# motherboardV2.net
KiCad netlist of a schematic drawn in EAGLE
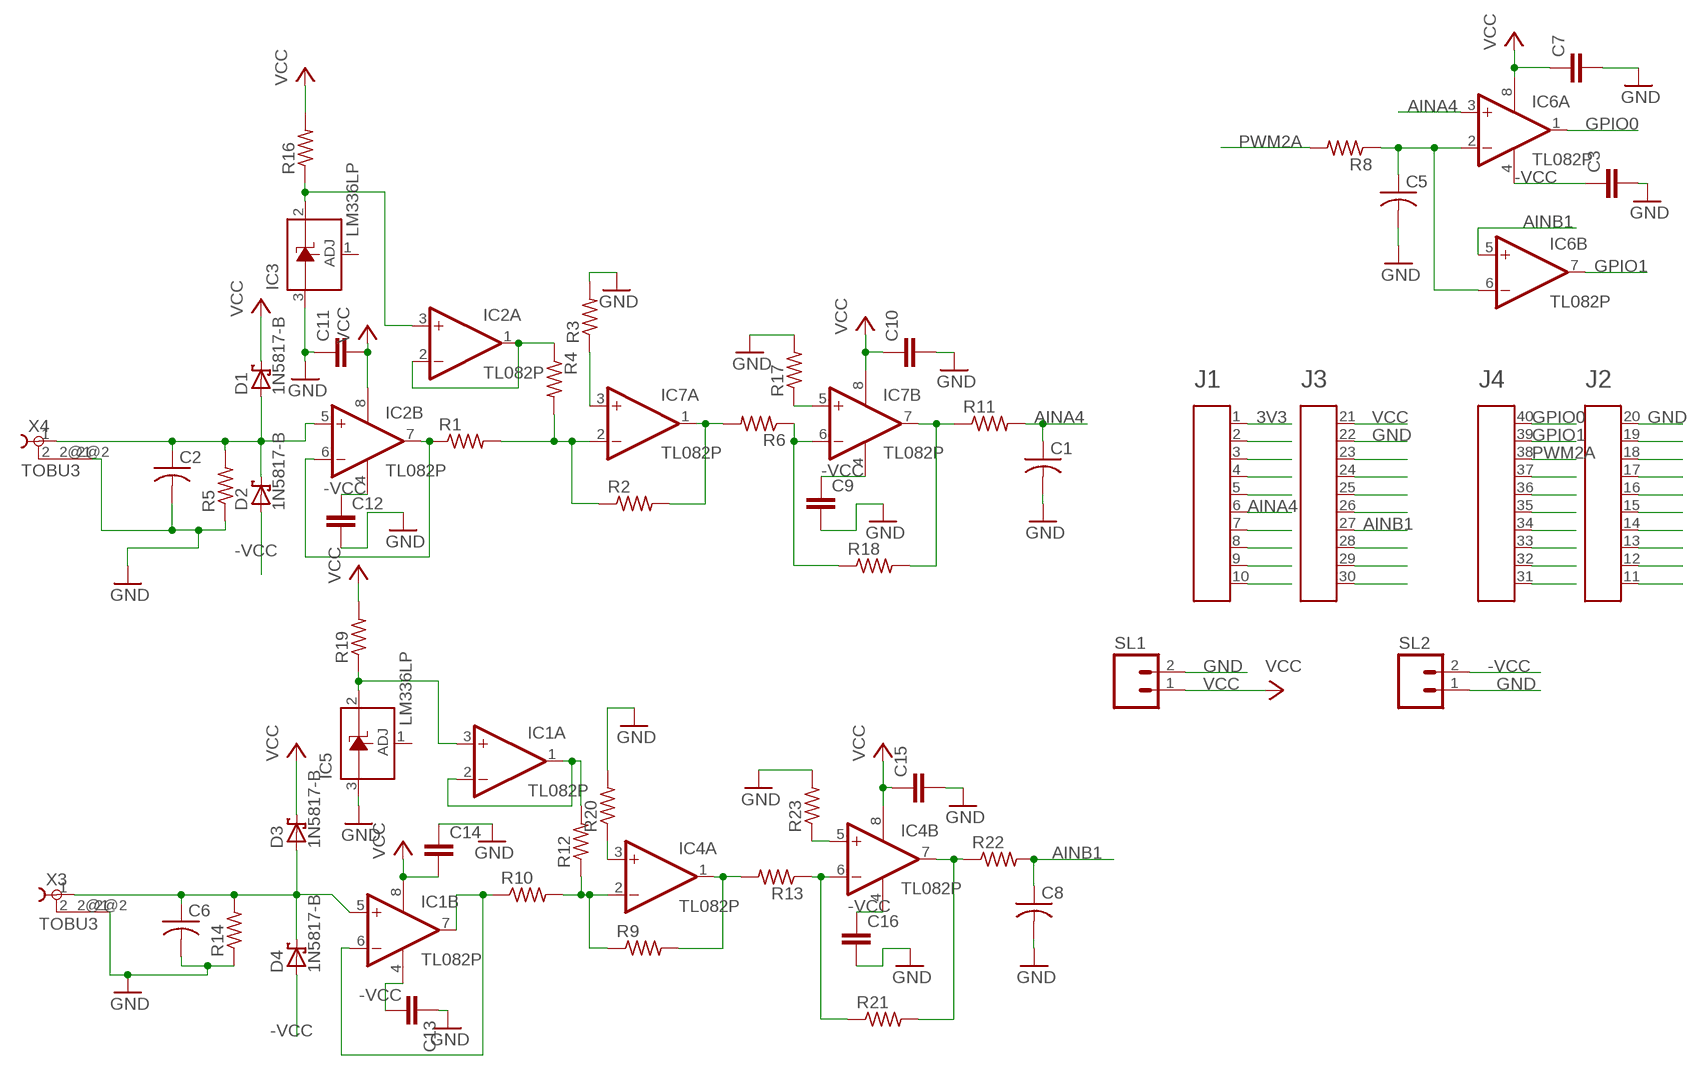
[diagram p0: schematic, sheet 1]

(export (version "E")
  (design (tool "Eeschema 10.0.6"))
  (components
    (comp (ref "A1")
      (value "HEADER4X10-BOOSTERPACK")
      (footprint "eagle-import:4X10-BOOSTERPACK")
      (libsource (lib "eagle-import") (part "HEADER4X10-BOOSTERPACK"))
    )
    (comp (ref "C1")
      (value "C-US025-025X050")
      (footprint "eagle-import:C025-025X050")
      (libsource (lib "eagle-import") (part "C-US025-025X050"))
    )
    (comp (ref "C2")
      (value "C-US025-025X050")
      (footprint "eagle-import:C025-025X050")
      (libsource (lib "eagle-import") (part "C-US025-025X050"))
    )
    (comp (ref "C3")
      (value "C-EU025-025X050")
      (footprint "eagle-import:C025-025X050")
      (libsource (lib "eagle-import") (part "C-EU025-025X050"))
    )
    (comp (ref "C5")
      (value "C-US025-025X050")
      (footprint "eagle-import:C025-025X050")
      (libsource (lib "eagle-import") (part "C-US025-025X050"))
    )
    (comp (ref "C6")
      (value "C-US025-025X050")
      (footprint "eagle-import:C025-025X050")
      (libsource (lib "eagle-import") (part "C-US025-025X050"))
    )
    (comp (ref "C7")
      (value "C-EU025-025X050")
      (footprint "eagle-import:C025-025X050")
      (libsource (lib "eagle-import") (part "C-EU025-025X050"))
    )
    (comp (ref "C8")
      (value "C-US025-025X050")
      (footprint "eagle-import:C025-025X050")
      (libsource (lib "eagle-import") (part "C-US025-025X050"))
    )
    (comp (ref "C9")
      (value "C-EU025-025X050")
      (footprint "eagle-import:C025-025X050")
      (libsource (lib "eagle-import") (part "C-EU025-025X050"))
    )
    (comp (ref "C10")
      (value "C-EU025-025X050")
      (footprint "eagle-import:C025-025X050")
      (libsource (lib "eagle-import") (part "C-EU025-025X050"))
    )
    (comp (ref "C11")
      (value "C-EU025-025X050")
      (footprint "eagle-import:C025-025X050")
      (libsource (lib "eagle-import") (part "C-EU025-025X050"))
    )
    (comp (ref "C12")
      (value "C-EU025-030X050")
      (footprint "eagle-import:C025-030X050")
      (libsource (lib "eagle-import") (part "C-EU025-030X050"))
    )
    (comp (ref "C13")
      (value "C-EU025-025X050")
      (footprint "eagle-import:C025-025X050")
      (libsource (lib "eagle-import") (part "C-EU025-025X050"))
    )
    (comp (ref "C14")
      (value "C-EU025-025X050")
      (footprint "eagle-import:C025-025X050")
      (libsource (lib "eagle-import") (part "C-EU025-025X050"))
    )
    (comp (ref "C15")
      (value "C-EU025-025X050")
      (footprint "eagle-import:C025-025X050")
      (libsource (lib "eagle-import") (part "C-EU025-025X050"))
    )
    (comp (ref "C16")
      (value "C-EU025-025X050")
      (footprint "eagle-import:C025-025X050")
      (libsource (lib "eagle-import") (part "C-EU025-025X050"))
    )
    (comp (ref "D1")
      (value "1N5817-B")
      (footprint "eagle-import:DO41-7.6")
      (libsource (lib "eagle-import") (part "1N5817-B"))
    )
    (comp (ref "D2")
      (value "1N5817-B")
      (footprint "eagle-import:DO41-7.6")
      (libsource (lib "eagle-import") (part "1N5817-B"))
    )
    (comp (ref "D3")
      (value "1N5817-B")
      (footprint "eagle-import:DO41-7.6")
      (libsource (lib "eagle-import") (part "1N5817-B"))
    )
    (comp (ref "D4")
      (value "1N5817-B")
      (footprint "eagle-import:DO41-7.6")
      (libsource (lib "eagle-import") (part "1N5817-B"))
    )
    (comp (ref "IC1")
      (value "TL082P")
      (footprint "eagle-import:DIL08")
      (libsource (lib "eagle-import") (part "TL082P"))
    )
    (comp (ref "IC2")
      (value "TL082P")
      (footprint "eagle-import:DIL08")
      (libsource (lib "eagle-import") (part "TL082P"))
    )
    (comp (ref "IC3")
      (value "LM336LP")
      (footprint "eagle-import:TO92")
      (libsource (lib "eagle-import") (part "LM336LP"))
    )
    (comp (ref "IC4")
      (value "TL082P")
      (footprint "eagle-import:DIL08")
      (libsource (lib "eagle-import") (part "TL082P"))
    )
    (comp (ref "IC5")
      (value "LM336LP")
      (footprint "eagle-import:TO92")
      (libsource (lib "eagle-import") (part "LM336LP"))
    )
    (comp (ref "IC6")
      (value "TL082P")
      (footprint "eagle-import:DIL08")
      (libsource (lib "eagle-import") (part "TL082P"))
    )
    (comp (ref "IC7")
      (value "TL082P")
      (footprint "eagle-import:DIL08")
      (libsource (lib "eagle-import") (part "TL082P"))
    )
    (comp (ref "R1")
      (value "R-US_0207/7")
      (footprint "eagle-import:0207_7")
      (libsource (lib "eagle-import") (part "resistor_R-US_0207/7"))
    )
    (comp (ref "R2")
      (value "R-US_0207/7")
      (footprint "eagle-import:0207_7")
      (libsource (lib "eagle-import") (part "resistor_R-US_0207/7"))
    )
    (comp (ref "R3")
      (value "R-US_0207/7")
      (footprint "eagle-import:0207_7")
      (libsource (lib "eagle-import") (part "resistor_R-US_0207/7"))
    )
    (comp (ref "R4")
      (value "R-US_0207/7")
      (footprint "eagle-import:0207_7")
      (libsource (lib "eagle-import") (part "resistor_R-US_0207/7"))
    )
    (comp (ref "R5")
      (value "R-US_0207/7")
      (footprint "eagle-import:0207_7")
      (libsource (lib "eagle-import") (part "resistor_R-US_0207/7"))
    )
    (comp (ref "R6")
      (value "R-US_0207/7")
      (footprint "eagle-import:0207_7")
      (libsource (lib "eagle-import") (part "resistor_R-US_0207/7"))
    )
    (comp (ref "R8")
      (value "R-US_0207/7")
      (footprint "eagle-import:0207_7")
      (libsource (lib "eagle-import") (part "R-US_0207/7"))
    )
    (comp (ref "R9")
      (value "R-US_0207/7")
      (footprint "eagle-import:0207_7")
      (libsource (lib "eagle-import") (part "resistor_R-US_0207/7"))
    )
    (comp (ref "R10")
      (value "R-US_0207/7")
      (footprint "eagle-import:0207_7")
      (libsource (lib "eagle-import") (part "resistor_R-US_0207/7"))
    )
    (comp (ref "R11")
      (value "R-US_0207/7")
      (footprint "eagle-import:0207_7")
      (libsource (lib "eagle-import") (part "resistor_R-US_0207/7"))
    )
    (comp (ref "R12")
      (value "R-US_0207/7")
      (footprint "eagle-import:0207_7")
      (libsource (lib "eagle-import") (part "resistor_R-US_0207/7"))
    )
    (comp (ref "R13")
      (value "R-US_0207/7")
      (footprint "eagle-import:0207_7")
      (libsource (lib "eagle-import") (part "resistor_R-US_0207/7"))
    )
    (comp (ref "R14")
      (value "R-US_0207/7")
      (footprint "eagle-import:0207_7")
      (libsource (lib "eagle-import") (part "resistor_R-US_0207/7"))
    )
    (comp (ref "R16")
      (value "R-US_0207/7")
      (footprint "eagle-import:0207_7")
      (libsource (lib "eagle-import") (part "R-US_0207/7"))
    )
    (comp (ref "R17")
      (value "R-US_0207/7")
      (footprint "eagle-import:0207_7")
      (libsource (lib "eagle-import") (part "resistor_R-US_0207/7"))
    )
    (comp (ref "R18")
      (value "R-US_0207/7")
      (footprint "eagle-import:0207_7")
      (libsource (lib "eagle-import") (part "resistor_R-US_0207/7"))
    )
    (comp (ref "R19")
      (value "R-US_0207/7")
      (footprint "eagle-import:0207_7")
      (libsource (lib "eagle-import") (part "R-US_0207/7"))
    )
    (comp (ref "R20")
      (value "R-US_0207/7")
      (footprint "eagle-import:0207_7")
      (libsource (lib "eagle-import") (part "R-US_0207/7"))
    )
    (comp (ref "R21")
      (value "R-US_0207/7")
      (footprint "eagle-import:0207_7")
      (libsource (lib "eagle-import") (part "R-US_0207/7"))
    )
    (comp (ref "R22")
      (value "R-US_0207/7")
      (footprint "eagle-import:0207_7")
      (libsource (lib "eagle-import") (part "R-US_0207/7"))
    )
    (comp (ref "R23")
      (value "R-US_0207/7")
      (footprint "eagle-import:0207_7")
      (libsource (lib "eagle-import") (part "R-US_0207/7"))
    )
    (comp (ref "SL1")
      (value "M02")
      (footprint "eagle-import:02P")
      (libsource (lib "eagle-import") (part "M02"))
    )
    (comp (ref "SL2")
      (value "M02")
      (footprint "eagle-import:02P")
      (libsource (lib "eagle-import") (part "M02"))
    )
    (comp (ref "X3")
      (value "TOBU3")
      (footprint "eagle-import:TOBU3")
      (libsource (lib "eagle-import") (part "TOBU3"))
    )
    (comp (ref "X4")
      (value "TOBU3")
      (footprint "eagle-import:TOBU3")
      (libsource (lib "eagle-import") (part "TOBU3"))
    )
  )
  (nets
    (net (code "1") (name "/-VCC") (class "Default")
      (node (ref "C12") (pin "1") (pinfunction "1_1") (pintype "passive"))
      (node (ref "C13") (pin "2") (pinfunction "2_2") (pintype "passive"))
      (node (ref "C16") (pin "1") (pinfunction "1_1") (pintype "passive"))
      (node (ref "C3") (pin "1") (pinfunction "1_1") (pintype "passive"))
      (node (ref "C9") (pin "1") (pinfunction "1_1") (pintype "passive"))
      (node (ref "D2") (pin "A") (pinfunction "A_A") (pintype "passive"))
      (node (ref "D4") (pin "A") (pinfunction "A_A") (pintype "passive"))
      (node (ref "IC1") (pin "4") (pinfunction "V-_4") (pintype "power_in"))
      (node (ref "IC2") (pin "4") (pinfunction "V-_4") (pintype "power_in"))
      (node (ref "IC4") (pin "4") (pinfunction "V-_4") (pintype "power_in"))
      (node (ref "IC6") (pin "4") (pinfunction "V-_4") (pintype "power_in"))
      (node (ref "IC7") (pin "4") (pinfunction "V-_4") (pintype "power_in"))
      (node (ref "SL2") (pin "2") (pinfunction "2_2") (pintype "passive"))
    )
    (net (code "2") (name "/3V3") (class "Default")
      (node (ref "A1") (pin "1") (pinfunction "P$1_1") (pintype "bidirectional"))
    )
    (net (code "3") (name "/AINA4") (class "Default")
      (node (ref "A1") (pin "6") (pinfunction "P$6_6") (pintype "bidirectional"))
      (node (ref "C1") (pin "1") (pinfunction "1_1") (pintype "passive"))
      (node (ref "IC6") (pin "3") (pinfunction "+IN_3") (pintype "input"))
      (node (ref "R11") (pin "2") (pinfunction "2_2") (pintype "passive"))
    )
    (net (code "4") (name "/AINB1") (class "Default")
      (node (ref "A1") (pin "27") (pinfunction "P$27_27") (pintype "bidirectional"))
      (node (ref "C8") (pin "1") (pinfunction "1_1") (pintype "passive"))
      (node (ref "IC6") (pin "5") (pinfunction "+IN_5") (pintype "input"))
      (node (ref "R22") (pin "2") (pinfunction "2_2") (pintype "passive"))
    )
    (net (code "5") (name "/GPIO0") (class "Default")
      (node (ref "A1") (pin "40") (pinfunction "P$40_40") (pintype "bidirectional"))
      (node (ref "IC6") (pin "1") (pinfunction "OUT_1") (pintype "output"))
    )
    (net (code "6") (name "/GPIO1") (class "Default")
      (node (ref "A1") (pin "39") (pinfunction "P$39_39") (pintype "bidirectional"))
      (node (ref "IC6") (pin "7") (pinfunction "OUT_7") (pintype "output"))
    )
    (net (code "7") (name "/PWM2A") (class "Default")
      (node (ref "A1") (pin "38") (pinfunction "P$38_38") (pintype "bidirectional"))
      (node (ref "R8") (pin "2") (pinfunction "2_2") (pintype "passive"))
    )
    (net (code "8") (name "GND") (class "Default")
      (node (ref "A1") (pin "20") (pinfunction "P$20_20") (pintype "bidirectional"))
      (node (ref "A1") (pin "22") (pinfunction "P$22_22") (pintype "bidirectional"))
      (node (ref "C1") (pin "2") (pinfunction "2_2") (pintype "passive"))
      (node (ref "C10") (pin "2") (pinfunction "2_2") (pintype "passive"))
      (node (ref "C11") (pin "1") (pinfunction "1_1") (pintype "passive"))
      (node (ref "C12") (pin "2") (pinfunction "2_2") (pintype "passive"))
      (node (ref "C13") (pin "1") (pinfunction "1_1") (pintype "passive"))
      (node (ref "C14") (pin "1") (pinfunction "1_1") (pintype "passive"))
      (node (ref "C15") (pin "2") (pinfunction "2_2") (pintype "passive"))
      (node (ref "C16") (pin "2") (pinfunction "2_2") (pintype "passive"))
      (node (ref "C2") (pin "2") (pinfunction "2_2") (pintype "passive"))
      (node (ref "C3") (pin "2") (pinfunction "2_2") (pintype "passive"))
      (node (ref "C5") (pin "2") (pinfunction "2_2") (pintype "passive"))
      (node (ref "C6") (pin "2") (pinfunction "2_2") (pintype "passive"))
      (node (ref "C7") (pin "2") (pinfunction "2_2") (pintype "passive"))
      (node (ref "C8") (pin "2") (pinfunction "2_2") (pintype "passive"))
      (node (ref "C9") (pin "2") (pinfunction "2_2") (pintype "passive"))
      (node (ref "IC3") (pin "3") (pinfunction "A_3") (pintype "input"))
      (node (ref "IC5") (pin "3") (pinfunction "A_3") (pintype "input"))
      (node (ref "R14") (pin "1") (pinfunction "1_1") (pintype "passive"))
      (node (ref "R17") (pin "2") (pinfunction "2_2") (pintype "passive"))
      (node (ref "R20") (pin "2") (pinfunction "2_2") (pintype "passive"))
      (node (ref "R23") (pin "2") (pinfunction "2_2") (pintype "passive"))
      (node (ref "R3") (pin "2") (pinfunction "2_2") (pintype "passive"))
      (node (ref "R5") (pin "1") (pinfunction "1_1") (pintype "passive"))
      (node (ref "SL1") (pin "2") (pinfunction "2_2") (pintype "passive"))
      (node (ref "SL2") (pin "1") (pinfunction "1_1") (pintype "passive"))
      (node (ref "X3") (pin "2@2") (pinfunction "4_2@2") (pintype "passive"))
      (node (ref "X4") (pin "2@2") (pinfunction "4_2@2") (pintype "passive"))
    )
    (net (code "9") (name "Net-(IC1A-+IN)") (class "Default")
      (node (ref "IC1") (pin "3") (pinfunction "+IN_3") (pintype "input"))
      (node (ref "IC5") (pin "2") (pinfunction "C_2") (pintype "passive"))
      (node (ref "R19") (pin "1") (pinfunction "1_1") (pintype "passive"))
    )
    (net (code "10") (name "Net-(IC1A--IN)") (class "Default")
      (node (ref "IC1") (pin "1") (pinfunction "OUT_1") (pintype "output"))
      (node (ref "IC1") (pin "2") (pinfunction "-IN_2") (pintype "input"))
      (node (ref "R12") (pin "2") (pinfunction "2_2") (pintype "passive"))
    )
    (net (code "11") (name "Net-(IC1B-+IN)") (class "Default")
      (node (ref "C6") (pin "1") (pinfunction "1_1") (pintype "passive"))
      (node (ref "D3") (pin "A") (pinfunction "A_A") (pintype "passive"))
      (node (ref "D4") (pin "C") (pinfunction "C_C") (pintype "passive"))
      (node (ref "IC1") (pin "5") (pinfunction "+IN_5") (pintype "input"))
      (node (ref "R14") (pin "2") (pinfunction "2_2") (pintype "passive"))
      (node (ref "X3") (pin "1") (pinfunction "1_1") (pintype "passive"))
    )
    (net (code "12") (name "Net-(IC1B--IN)") (class "Default")
      (node (ref "IC1") (pin "6") (pinfunction "-IN_6") (pintype "input"))
      (node (ref "IC1") (pin "7") (pinfunction "OUT_7") (pintype "output"))
      (node (ref "R10") (pin "1") (pinfunction "1_1") (pintype "passive"))
    )
    (net (code "13") (name "Net-(IC2A-+IN)") (class "Default")
      (node (ref "IC2") (pin "3") (pinfunction "+IN_3") (pintype "input"))
      (node (ref "IC3") (pin "2") (pinfunction "C_2") (pintype "passive"))
      (node (ref "R16") (pin "1") (pinfunction "1_1") (pintype "passive"))
    )
    (net (code "14") (name "Net-(IC2A--IN)") (class "Default")
      (node (ref "IC2") (pin "1") (pinfunction "OUT_1") (pintype "output"))
      (node (ref "IC2") (pin "2") (pinfunction "-IN_2") (pintype "input"))
      (node (ref "R4") (pin "1") (pinfunction "1_1") (pintype "passive"))
    )
    (net (code "15") (name "Net-(IC2B-+IN)") (class "Default")
      (node (ref "C2") (pin "1") (pinfunction "1_1") (pintype "passive"))
      (node (ref "D1") (pin "A") (pinfunction "A_A") (pintype "passive"))
      (node (ref "D2") (pin "C") (pinfunction "C_C") (pintype "passive"))
      (node (ref "IC2") (pin "5") (pinfunction "+IN_5") (pintype "input"))
      (node (ref "R5") (pin "2") (pinfunction "2_2") (pintype "passive"))
      (node (ref "X4") (pin "1") (pinfunction "1_1") (pintype "passive"))
    )
    (net (code "16") (name "Net-(IC2B--IN)") (class "Default")
      (node (ref "IC2") (pin "6") (pinfunction "-IN_6") (pintype "input"))
      (node (ref "IC2") (pin "7") (pinfunction "OUT_7") (pintype "output"))
      (node (ref "R1") (pin "1") (pinfunction "1_1") (pintype "passive"))
    )
    (net (code "17") (name "Net-(IC4A-+IN)") (class "Default")
      (node (ref "IC4") (pin "3") (pinfunction "+IN_3") (pintype "input"))
      (node (ref "R20") (pin "1") (pinfunction "1_1") (pintype "passive"))
    )
    (net (code "18") (name "Net-(IC4A--IN)") (class "Default")
      (node (ref "IC4") (pin "2") (pinfunction "-IN_2") (pintype "input"))
      (node (ref "R10") (pin "2") (pinfunction "2_2") (pintype "passive"))
      (node (ref "R12") (pin "1") (pinfunction "1_1") (pintype "passive"))
      (node (ref "R9") (pin "1") (pinfunction "1_1") (pintype "passive"))
    )
    (net (code "19") (name "Net-(IC4A-OUT)") (class "Default")
      (node (ref "IC4") (pin "1") (pinfunction "OUT_1") (pintype "output"))
      (node (ref "R13") (pin "2") (pinfunction "2_2") (pintype "passive"))
      (node (ref "R9") (pin "2") (pinfunction "2_2") (pintype "passive"))
    )
    (net (code "20") (name "Net-(IC4B-+IN)") (class "Default")
      (node (ref "IC4") (pin "5") (pinfunction "+IN_5") (pintype "input"))
      (node (ref "R23") (pin "1") (pinfunction "1_1") (pintype "passive"))
    )
    (net (code "21") (name "Net-(IC4B--IN)") (class "Default")
      (node (ref "IC4") (pin "6") (pinfunction "-IN_6") (pintype "input"))
      (node (ref "R13") (pin "1") (pinfunction "1_1") (pintype "passive"))
      (node (ref "R21") (pin "1") (pinfunction "1_1") (pintype "passive"))
    )
    (net (code "22") (name "Net-(IC4B-OUT)") (class "Default")
      (node (ref "IC4") (pin "7") (pinfunction "OUT_7") (pintype "output"))
      (node (ref "R21") (pin "2") (pinfunction "2_2") (pintype "passive"))
      (node (ref "R22") (pin "1") (pinfunction "1_1") (pintype "passive"))
    )
    (net (code "23") (name "Net-(IC6A--IN)") (class "Default")
      (node (ref "C5") (pin "1") (pinfunction "1_1") (pintype "passive"))
      (node (ref "IC6") (pin "2") (pinfunction "-IN_2") (pintype "input"))
      (node (ref "IC6") (pin "6") (pinfunction "-IN_6") (pintype "input"))
      (node (ref "R8") (pin "1") (pinfunction "1_1") (pintype "passive"))
    )
    (net (code "24") (name "Net-(IC7A-+IN)") (class "Default")
      (node (ref "IC7") (pin "3") (pinfunction "+IN_3") (pintype "input"))
      (node (ref "R3") (pin "1") (pinfunction "1_1") (pintype "passive"))
    )
    (net (code "25") (name "Net-(IC7A--IN)") (class "Default")
      (node (ref "IC7") (pin "2") (pinfunction "-IN_2") (pintype "input"))
      (node (ref "R1") (pin "2") (pinfunction "2_2") (pintype "passive"))
      (node (ref "R2") (pin "1") (pinfunction "1_1") (pintype "passive"))
      (node (ref "R4") (pin "2") (pinfunction "2_2") (pintype "passive"))
    )
    (net (code "26") (name "Net-(IC7A-OUT)") (class "Default")
      (node (ref "IC7") (pin "1") (pinfunction "OUT_1") (pintype "output"))
      (node (ref "R2") (pin "2") (pinfunction "2_2") (pintype "passive"))
      (node (ref "R6") (pin "2") (pinfunction "2_2") (pintype "passive"))
    )
    (net (code "27") (name "Net-(IC7B-+IN)") (class "Default")
      (node (ref "IC7") (pin "5") (pinfunction "+IN_5") (pintype "input"))
      (node (ref "R17") (pin "1") (pinfunction "1_1") (pintype "passive"))
    )
    (net (code "28") (name "Net-(IC7B--IN)") (class "Default")
      (node (ref "IC7") (pin "6") (pinfunction "-IN_6") (pintype "input"))
      (node (ref "R18") (pin "1") (pinfunction "1_1") (pintype "passive"))
      (node (ref "R6") (pin "1") (pinfunction "1_1") (pintype "passive"))
    )
    (net (code "29") (name "Net-(IC7B-OUT)") (class "Default")
      (node (ref "IC7") (pin "7") (pinfunction "OUT_7") (pintype "output"))
      (node (ref "R11") (pin "1") (pinfunction "1_1") (pintype "passive"))
      (node (ref "R18") (pin "2") (pinfunction "2_2") (pintype "passive"))
    )
    (net (code "30") (name "VCC") (class "Default")
      (node (ref "A1") (pin "21") (pinfunction "P$21_21") (pintype "bidirectional"))
      (node (ref "C10") (pin "1") (pinfunction "1_1") (pintype "passive"))
      (node (ref "C11") (pin "2") (pinfunction "2_2") (pintype "passive"))
      (node (ref "C14") (pin "2") (pinfunction "2_2") (pintype "passive"))
      (node (ref "C15") (pin "1") (pinfunction "1_1") (pintype "passive"))
      (node (ref "C7") (pin "1") (pinfunction "1_1") (pintype "passive"))
      (node (ref "D1") (pin "C") (pinfunction "C_C") (pintype "passive"))
      (node (ref "D3") (pin "C") (pinfunction "C_C") (pintype "passive"))
      (node (ref "IC1") (pin "8") (pinfunction "V+_8") (pintype "power_in"))
      (node (ref "IC2") (pin "8") (pinfunction "V+_8") (pintype "power_in"))
      (node (ref "IC4") (pin "8") (pinfunction "V+_8") (pintype "power_in"))
      (node (ref "IC6") (pin "8") (pinfunction "V+_8") (pintype "power_in"))
      (node (ref "IC7") (pin "8") (pinfunction "V+_8") (pintype "power_in"))
      (node (ref "R16") (pin "2") (pinfunction "2_2") (pintype "passive"))
      (node (ref "R19") (pin "2") (pinfunction "2_2") (pintype "passive"))
      (node (ref "SL1") (pin "1") (pinfunction "1_1") (pintype "passive"))
    )
    (net (code "31") (name "unconnected-(A1-P$2-Pad2)") (class "Default")
      (node (ref "A1") (pin "2") (pinfunction "P$2_2") (pintype "bidirectional"))
    )
    (net (code "32") (name "unconnected-(A1-P$3-Pad3)") (class "Default")
      (node (ref "A1") (pin "3") (pinfunction "P$3_3") (pintype "bidirectional"))
    )
    (net (code "33") (name "unconnected-(A1-P$4-Pad4)") (class "Default")
      (node (ref "A1") (pin "4") (pinfunction "P$4_4") (pintype "bidirectional"))
    )
    (net (code "34") (name "unconnected-(A1-P$5-Pad5)") (class "Default")
      (node (ref "A1") (pin "5") (pinfunction "P$5_5") (pintype "bidirectional"))
    )
    (net (code "35") (name "unconnected-(A1-P$7-Pad7)") (class "Default")
      (node (ref "A1") (pin "7") (pinfunction "P$7_7") (pintype "bidirectional"))
    )
    (net (code "36") (name "unconnected-(A1-P$8-Pad8)") (class "Default")
      (node (ref "A1") (pin "8") (pinfunction "P$8_8") (pintype "bidirectional"))
    )
    (net (code "37") (name "unconnected-(A1-P$9-Pad9)") (class "Default")
      (node (ref "A1") (pin "9") (pinfunction "P$9_9") (pintype "bidirectional"))
    )
    (net (code "38") (name "unconnected-(A1-P$10-Pad10)") (class "Default")
      (node (ref "A1") (pin "10") (pinfunction "P$10_10") (pintype "bidirectional"))
    )
    (net (code "39") (name "unconnected-(A1-P$11-Pad11)") (class "Default")
      (node (ref "A1") (pin "11") (pinfunction "P$11_11") (pintype "bidirectional"))
    )
    (net (code "40") (name "unconnected-(A1-P$12-Pad12)") (class "Default")
      (node (ref "A1") (pin "12") (pinfunction "P$12_12") (pintype "bidirectional"))
    )
    (net (code "41") (name "unconnected-(A1-P$13-Pad13)") (class "Default")
      (node (ref "A1") (pin "13") (pinfunction "P$13_13") (pintype "bidirectional"))
    )
    (net (code "42") (name "unconnected-(A1-P$14-Pad14)") (class "Default")
      (node (ref "A1") (pin "14") (pinfunction "P$14_14") (pintype "bidirectional"))
    )
    (net (code "43") (name "unconnected-(A1-P$15-Pad15)") (class "Default")
      (node (ref "A1") (pin "15") (pinfunction "P$15_15") (pintype "bidirectional"))
    )
    (net (code "44") (name "unconnected-(A1-P$16-Pad16)") (class "Default")
      (node (ref "A1") (pin "16") (pinfunction "P$16_16") (pintype "bidirectional"))
    )
    (net (code "45") (name "unconnected-(A1-P$17-Pad17)") (class "Default")
      (node (ref "A1") (pin "17") (pinfunction "P$17_17") (pintype "bidirectional"))
    )
    (net (code "46") (name "unconnected-(A1-P$18-Pad18)") (class "Default")
      (node (ref "A1") (pin "18") (pinfunction "P$18_18") (pintype "bidirectional"))
    )
    (net (code "47") (name "unconnected-(A1-P$19-Pad19)") (class "Default")
      (node (ref "A1") (pin "19") (pinfunction "P$19_19") (pintype "bidirectional"))
    )
    (net (code "48") (name "unconnected-(A1-P$23-Pad23)") (class "Default")
      (node (ref "A1") (pin "23") (pinfunction "P$23_23") (pintype "bidirectional"))
    )
    (net (code "49") (name "unconnected-(A1-P$24-Pad24)") (class "Default")
      (node (ref "A1") (pin "24") (pinfunction "P$24_24") (pintype "bidirectional"))
    )
    (net (code "50") (name "unconnected-(A1-P$25-Pad25)") (class "Default")
      (node (ref "A1") (pin "25") (pinfunction "P$25_25") (pintype "bidirectional"))
    )
    (net (code "51") (name "unconnected-(A1-P$26-Pad26)") (class "Default")
      (node (ref "A1") (pin "26") (pinfunction "P$26_26") (pintype "bidirectional"))
    )
    (net (code "52") (name "unconnected-(A1-P$28-Pad28)") (class "Default")
      (node (ref "A1") (pin "28") (pinfunction "P$28_28") (pintype "bidirectional"))
    )
    (net (code "53") (name "unconnected-(A1-P$29-Pad29)") (class "Default")
      (node (ref "A1") (pin "29") (pinfunction "P$29_29") (pintype "bidirectional"))
    )
    (net (code "54") (name "unconnected-(A1-P$30-Pad30)") (class "Default")
      (node (ref "A1") (pin "30") (pinfunction "P$30_30") (pintype "bidirectional"))
    )
    (net (code "55") (name "unconnected-(A1-P$31-Pad31)") (class "Default")
      (node (ref "A1") (pin "31") (pinfunction "P$31_31") (pintype "bidirectional"))
    )
    (net (code "56") (name "unconnected-(A1-P$32-Pad32)") (class "Default")
      (node (ref "A1") (pin "32") (pinfunction "P$32_32") (pintype "bidirectional"))
    )
    (net (code "57") (name "unconnected-(A1-P$33-Pad33)") (class "Default")
      (node (ref "A1") (pin "33") (pinfunction "P$33_33") (pintype "bidirectional"))
    )
    (net (code "58") (name "unconnected-(A1-P$34-Pad34)") (class "Default")
      (node (ref "A1") (pin "34") (pinfunction "P$34_34") (pintype "bidirectional"))
    )
    (net (code "59") (name "unconnected-(A1-P$35-Pad35)") (class "Default")
      (node (ref "A1") (pin "35") (pinfunction "P$35_35") (pintype "bidirectional"))
    )
    (net (code "60") (name "unconnected-(A1-P$36-Pad36)") (class "Default")
      (node (ref "A1") (pin "36") (pinfunction "P$36_36") (pintype "bidirectional"))
    )
    (net (code "61") (name "unconnected-(A1-P$37-Pad37)") (class "Default")
      (node (ref "A1") (pin "37") (pinfunction "P$37_37") (pintype "bidirectional"))
    )
    (net (code "62") (name "unconnected-(IC3-ADJ-Pad1)") (class "Default")
      (node (ref "IC3") (pin "1") (pinfunction "ADJ_1") (pintype "input"))
    )
    (net (code "63") (name "unconnected-(IC5-ADJ-Pad1)") (class "Default")
      (node (ref "IC5") (pin "1") (pinfunction "ADJ_1") (pintype "input"))
    )
    (net (code "64") (name "unconnected-(X3-3-Pad2@1)") (class "Default")
      (node (ref "X3") (pin "2@1") (pinfunction "3_2@1") (pintype "passive"))
    )
    (net (code "65") (name "unconnected-(X3-Pad2)") (class "Default")
      (node (ref "X3") (pin "2") (pinfunction "2_2") (pintype "passive"))
    )
    (net (code "66") (name "unconnected-(X4-3-Pad2@1)") (class "Default")
      (node (ref "X4") (pin "2@1") (pinfunction "3_2@1") (pintype "passive"))
    )
    (net (code "67") (name "unconnected-(X4-Pad2)") (class "Default")
      (node (ref "X4") (pin "2") (pinfunction "2_2") (pintype "passive"))
    )
  )
)
